# schematic.net
KiCad netlist of a schematic drawn in Altium Designer
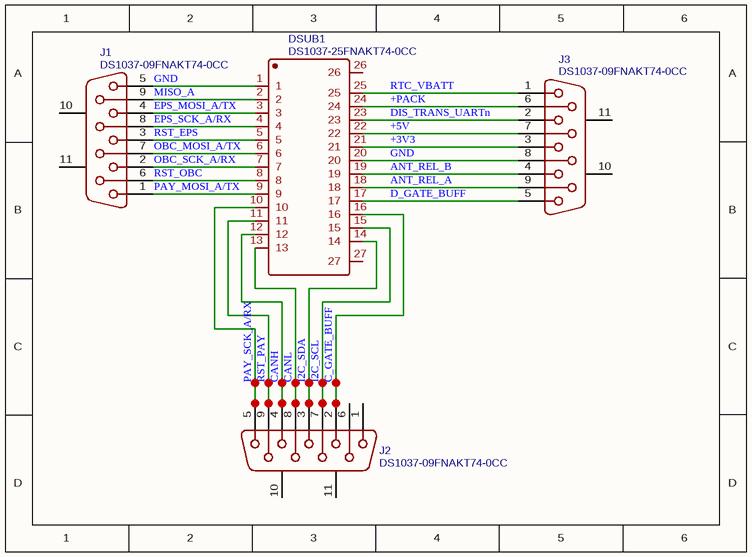
[diagram p0: schematic.schdoc]

(export (version "E")
  (design (tool "Eeschema 10.0.6"))
  (components
    (comp (ref "DSUB1")
      (value "DS1037-25FNAKT74-0CC")
      (fields (field (name "BOM_SUPPLIER PART") "C77838"))
      (libsource (lib "altium-import") (part "root_0_DS1037-25FNAKT74-0CC_"))
    )
    (comp (ref "J1")
      (value "DS1037-09FNAKT74-0CC")
      (fields (field (name "BOM_SUPPLIER PART") "C75749"))
      (libsource (lib "altium-import") (part "root_1_DS1037-09FNAKT74-0CC_"))
    )
    (comp (ref "J2")
      (value "DS1037-09FNAKT74-0CC")
      (fields (field (name "BOM_SUPPLIER PART") "C75749"))
      (libsource (lib "altium-import") (part "root_2_DS1037-09FNAKT74-0CC_"))
    )
    (comp (ref "J3")
      (value "DS1037-09FNAKT74-0CC")
      (fields (field (name "BOM_SUPPLIER PART") "C75749"))
      (libsource (lib "altium-import") (part "root_3_DS1037-09FNAKT74-0CC_"))
    )
  )
  (nets
    (net (code "1") (name "/+3V3") (class "Default")
      (node (ref "DSUB1") (pin "21") (pinfunction "21_21") (pintype "passive"))
      (node (ref "J3") (pin "3") (pinfunction "3_3") (pintype "passive"))
    )
    (net (code "2") (name "/+5V") (class "Default")
      (node (ref "DSUB1") (pin "22") (pinfunction "22_22") (pintype "passive"))
      (node (ref "J3") (pin "7") (pinfunction "7_7") (pintype "passive"))
    )
    (net (code "3") (name "/+PACK") (class "Default")
      (node (ref "DSUB1") (pin "24") (pinfunction "24_24") (pintype "passive"))
      (node (ref "J3") (pin "6") (pinfunction "6_6") (pintype "passive"))
    )
    (net (code "4") (name "/ANT_REL_A") (class "Default")
      (node (ref "DSUB1") (pin "18") (pinfunction "18_18") (pintype "passive"))
      (node (ref "J3") (pin "9") (pinfunction "9_9") (pintype "passive"))
    )
    (net (code "5") (name "/ANT_REL_B") (class "Default")
      (node (ref "DSUB1") (pin "19") (pinfunction "19_19") (pintype "passive"))
      (node (ref "J3") (pin "4") (pinfunction "4_4") (pintype "passive"))
    )
    (net (code "6") (name "/CANH") (class "Default")
      (node (ref "DSUB1") (pin "12") (pinfunction "12_12") (pintype "passive"))
      (node (ref "J2") (pin "4") (pinfunction "4_4") (pintype "passive"))
    )
    (net (code "7") (name "/CANL") (class "Default")
      (node (ref "DSUB1") (pin "13") (pinfunction "13_13") (pintype "passive"))
      (node (ref "J2") (pin "8") (pinfunction "8_8") (pintype "passive"))
    )
    (net (code "8") (name "/C_GATE_BUFF") (class "Default")
      (node (ref "DSUB1") (pin "16") (pinfunction "16_16") (pintype "passive"))
      (node (ref "J2") (pin "2") (pinfunction "2_2") (pintype "passive"))
    )
    (net (code "9") (name "/DIS_TRANS_UARTn") (class "Default")
      (node (ref "DSUB1") (pin "23") (pinfunction "23_23") (pintype "passive"))
      (node (ref "J3") (pin "2") (pinfunction "2_2") (pintype "passive"))
    )
    (net (code "10") (name "/D_GATE_BUFF") (class "Default")
      (node (ref "DSUB1") (pin "17") (pinfunction "17_17") (pintype "passive"))
      (node (ref "J3") (pin "5") (pinfunction "5_5") (pintype "passive"))
    )
    (net (code "11") (name "/EPS_MOSI_A{slash}TX") (class "Default")
      (node (ref "DSUB1") (pin "3") (pinfunction "3_3") (pintype "passive"))
      (node (ref "J1") (pin "4") (pinfunction "4_4") (pintype "passive"))
    )
    (net (code "12") (name "/EPS_SCK_A{slash}RX") (class "Default")
      (node (ref "DSUB1") (pin "4") (pinfunction "4_4") (pintype "passive"))
      (node (ref "J1") (pin "8") (pinfunction "8_8") (pintype "passive"))
    )
    (net (code "13") (name "/GND") (class "Default")
      (node (ref "DSUB1") (pin "1") (pinfunction "1_1") (pintype "passive"))
      (node (ref "DSUB1") (pin "20") (pinfunction "20_20") (pintype "passive"))
      (node (ref "J1") (pin "5") (pinfunction "5_5") (pintype "passive"))
      (node (ref "J3") (pin "8") (pinfunction "8_8") (pintype "passive"))
    )
    (net (code "14") (name "/I2C_SCL") (class "Default")
      (node (ref "DSUB1") (pin "15") (pinfunction "15_15") (pintype "passive"))
      (node (ref "J2") (pin "7") (pinfunction "7_7") (pintype "passive"))
    )
    (net (code "15") (name "/I2C_SDA") (class "Default")
      (node (ref "DSUB1") (pin "14") (pinfunction "14_14") (pintype "passive"))
      (node (ref "J2") (pin "3") (pinfunction "3_3") (pintype "passive"))
    )
    (net (code "16") (name "/MISO_A") (class "Default")
      (node (ref "DSUB1") (pin "2") (pinfunction "2_2") (pintype "passive"))
      (node (ref "J1") (pin "9") (pinfunction "9_9") (pintype "passive"))
    )
    (net (code "17") (name "/OBC_MOSI_A{slash}TX") (class "Default")
      (node (ref "DSUB1") (pin "6") (pinfunction "6_6") (pintype "passive"))
      (node (ref "J1") (pin "7") (pinfunction "7_7") (pintype "passive"))
    )
    (net (code "18") (name "/OBC_SCK_A{slash}RX") (class "Default")
      (node (ref "DSUB1") (pin "7") (pinfunction "7_7") (pintype "passive"))
      (node (ref "J1") (pin "2") (pinfunction "2_2") (pintype "passive"))
    )
    (net (code "19") (name "/PAY_MOSI_A{slash}TX") (class "Default")
      (node (ref "DSUB1") (pin "9") (pinfunction "9_9") (pintype "passive"))
      (node (ref "J1") (pin "1") (pinfunction "1_1") (pintype "passive"))
    )
    (net (code "20") (name "/PAY_SCK_A{slash}RX") (class "Default")
      (node (ref "DSUB1") (pin "10") (pinfunction "10_10") (pintype "passive"))
      (node (ref "J2") (pin "5") (pinfunction "5_5") (pintype "passive"))
    )
    (net (code "21") (name "/RST_EPS") (class "Default")
      (node (ref "DSUB1") (pin "5") (pinfunction "5_5") (pintype "passive"))
      (node (ref "J1") (pin "3") (pinfunction "3_3") (pintype "passive"))
    )
    (net (code "22") (name "/RST_OBC") (class "Default")
      (node (ref "DSUB1") (pin "8") (pinfunction "8_8") (pintype "passive"))
      (node (ref "J1") (pin "6") (pinfunction "6_6") (pintype "passive"))
    )
    (net (code "23") (name "/RST_PAY") (class "Default")
      (node (ref "DSUB1") (pin "11") (pinfunction "11_11") (pintype "passive"))
      (node (ref "J2") (pin "9") (pinfunction "9_9") (pintype "passive"))
    )
    (net (code "24") (name "/RTC_VBATT") (class "Default")
      (node (ref "DSUB1") (pin "25") (pinfunction "25_25") (pintype "passive"))
      (node (ref "J3") (pin "1") (pinfunction "1_1") (pintype "passive"))
    )
    (net (code "25") (name "unconnected-(DSUB1-Pad26)") (class "Default")
      (node (ref "DSUB1") (pin "26") (pinfunction "26_26") (pintype "passive"))
    )
    (net (code "26") (name "unconnected-(DSUB1-Pad27)") (class "Default")
      (node (ref "DSUB1") (pin "27") (pinfunction "27_27") (pintype "passive"))
    )
    (net (code "27") (name "unconnected-(J1-MH1-Pad10)") (class "Default")
      (node (ref "J1") (pin "10") (pinfunction "MH1_10") (pintype "passive"))
    )
    (net (code "28") (name "unconnected-(J1-MH2-Pad11)") (class "Default")
      (node (ref "J1") (pin "11") (pinfunction "MH2_11") (pintype "passive"))
    )
    (net (code "29") (name "unconnected-(J2-MH1-Pad10)") (class "Default")
      (node (ref "J2") (pin "10") (pinfunction "MH1_10") (pintype "passive"))
    )
    (net (code "30") (name "unconnected-(J2-MH2-Pad11)") (class "Default")
      (node (ref "J2") (pin "11") (pinfunction "MH2_11") (pintype "passive"))
    )
    (net (code "31") (name "unconnected-(J2-Pad1)") (class "Default")
      (node (ref "J2") (pin "1") (pinfunction "1_1") (pintype "passive"))
    )
    (net (code "32") (name "unconnected-(J2-Pad6)") (class "Default")
      (node (ref "J2") (pin "6") (pinfunction "6_6") (pintype "passive"))
    )
    (net (code "33") (name "unconnected-(J3-MH1-Pad10)") (class "Default")
      (node (ref "J3") (pin "10") (pinfunction "MH1_10") (pintype "passive"))
    )
    (net (code "34") (name "unconnected-(J3-MH2-Pad11)") (class "Default")
      (node (ref "J3") (pin "11") (pinfunction "MH2_11") (pintype "passive"))
    )
  )
)
